# node.net
KiCad netlist of a schematic drawn in EAGLE
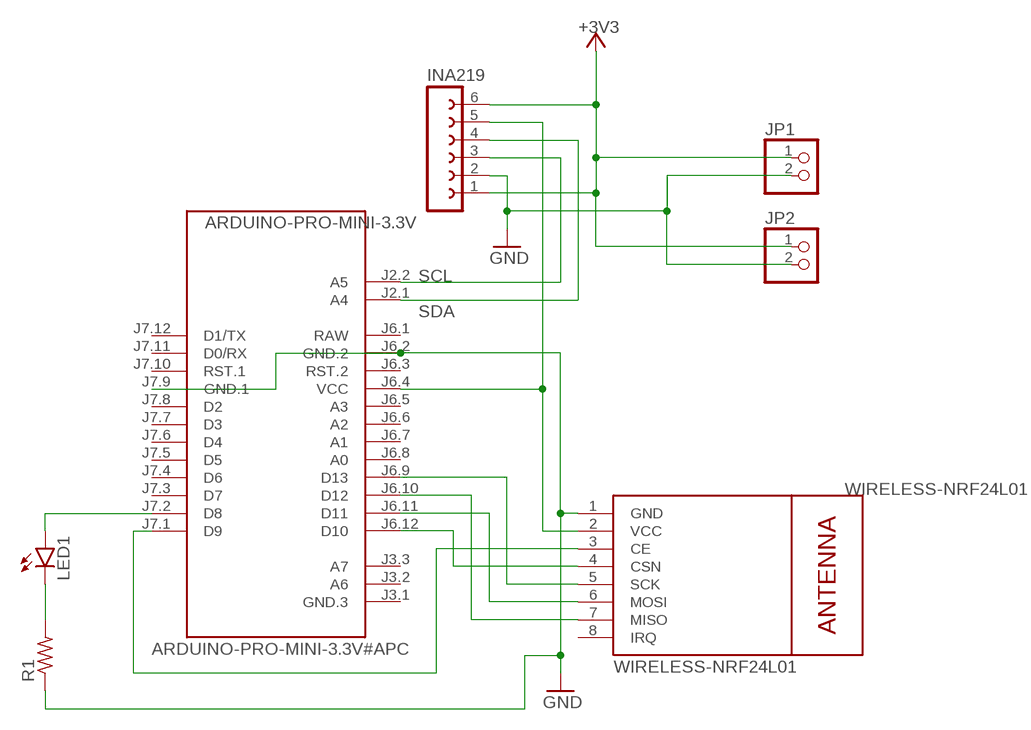
[diagram p0: schematic, sheet 1]

(export (version "E")
  (design (tool "Eeschema 10.0.6"))
  (components
    (comp (ref "ARDUINO-PRO-MINI-3.3V")
      (value "ARDUINO-PRO-MINI-3.3V#APC")
      (footprint "eagle-import:ARDUINO-PRO-MINI#APC")
      (libsource (lib "eagle-import") (part "ARDUINO-PRO-MINI-#APC3.3V"))
    )
    (comp (ref "INA219")
      (value "FE06-1")
      (footprint "eagle-import:FE06")
      (libsource (lib "eagle-import") (part "FE06-1"))
    )
    (comp (ref "JP1")
      (value "PINHD-1X2")
      (footprint "eagle-import:1X02")
      (libsource (lib "eagle-import") (part "PINHD-1X2"))
    )
    (comp (ref "JP2")
      (value "PINHD-1X2")
      (footprint "eagle-import:1X02")
      (libsource (lib "eagle-import") (part "PINHD-1X2"))
    )
    (comp (ref "LED1")
      (value "LED3MM")
      (footprint "eagle-import:LED3MM")
      (libsource (lib "eagle-import") (part "LED3MM"))
    )
    (comp (ref "R1")
      (value "R-US_0204/7")
      (footprint "eagle-import:0204_7")
      (libsource (lib "eagle-import") (part "R-US_0204/7"))
    )
    (comp (ref "WIRELESS-NRF24L01")
      (value "WIRELESS-NRF24L01")
      (footprint "eagle-import:WIRELESS-NRF24L01")
      (libsource (lib "eagle-import") (part "WIRELESS-NRF24L01"))
    )
  )
  (nets
    (net (code "1") (name "+3V3") (class "Default")
      (node (ref "INA219") (pin "1") (pinfunction "1_1") (pintype "passive"))
      (node (ref "INA219") (pin "6") (pinfunction "6_6") (pintype "passive"))
      (node (ref "JP1") (pin "1") (pinfunction "1_1") (pintype "passive"))
      (node (ref "JP2") (pin "1") (pinfunction "1_1") (pintype "passive"))
    )
    (net (code "2") (name "/RAW") (class "Default")
      (node (ref "ARDUINO-PRO-MINI-3.3V") (pin "J6.1") (pinfunction "RAW_J6.1") (pintype "power_in"))
    )
    (net (code "3") (name "/SCL") (class "Default")
      (node (ref "ARDUINO-PRO-MINI-3.3V") (pin "J2.2") (pinfunction "A5_J2.2") (pintype "bidirectional"))
      (node (ref "INA219") (pin "3") (pinfunction "3_3") (pintype "passive"))
    )
    (net (code "4") (name "/SDA") (class "Default")
      (node (ref "ARDUINO-PRO-MINI-3.3V") (pin "J2.1") (pinfunction "A4_J2.1") (pintype "bidirectional"))
      (node (ref "INA219") (pin "4") (pinfunction "4_4") (pintype "passive"))
    )
    (net (code "5") (name "GND") (class "Default")
      (node (ref "ARDUINO-PRO-MINI-3.3V") (pin "J6.2") (pinfunction "GND.2_J6.2") (pintype "power_in"))
      (node (ref "ARDUINO-PRO-MINI-3.3V") (pin "J7.9") (pinfunction "GND.1_J7.9") (pintype "power_in"))
      (node (ref "INA219") (pin "2") (pinfunction "2_2") (pintype "passive"))
      (node (ref "JP1") (pin "2") (pinfunction "2_2") (pintype "passive"))
      (node (ref "JP2") (pin "2") (pinfunction "2_2") (pintype "passive"))
      (node (ref "R1") (pin "1") (pinfunction "1_1") (pintype "passive"))
      (node (ref "WIRELESS-NRF24L01") (pin "1") (pinfunction "GND_1") (pintype "power_in"))
    )
    (net (code "6") (name "Net-(ARDUINO-PRO-MINI-3.3V-D8)") (class "Default")
      (node (ref "ARDUINO-PRO-MINI-3.3V") (pin "J7.2") (pinfunction "D8_J7.2") (pintype "bidirectional"))
      (node (ref "LED1") (pin "A") (pinfunction "A_A") (pintype "passive"))
    )
    (net (code "7") (name "Net-(ARDUINO-PRO-MINI-3.3V-D9)") (class "Default")
      (node (ref "ARDUINO-PRO-MINI-3.3V") (pin "J7.1") (pinfunction "D9_J7.1") (pintype "bidirectional"))
      (node (ref "WIRELESS-NRF24L01") (pin "3") (pinfunction "CE_3") (pintype "bidirectional"))
    )
    (net (code "8") (name "Net-(ARDUINO-PRO-MINI-3.3V-D10)") (class "Default")
      (node (ref "ARDUINO-PRO-MINI-3.3V") (pin "J6.12") (pinfunction "D10_J6.12") (pintype "bidirectional"))
      (node (ref "WIRELESS-NRF24L01") (pin "4") (pinfunction "CSN_4") (pintype "bidirectional"))
    )
    (net (code "9") (name "Net-(ARDUINO-PRO-MINI-3.3V-D11)") (class "Default")
      (node (ref "ARDUINO-PRO-MINI-3.3V") (pin "J6.11") (pinfunction "D11_J6.11") (pintype "bidirectional"))
      (node (ref "WIRELESS-NRF24L01") (pin "6") (pinfunction "MOSI_6") (pintype "bidirectional"))
    )
    (net (code "10") (name "Net-(ARDUINO-PRO-MINI-3.3V-D12)") (class "Default")
      (node (ref "ARDUINO-PRO-MINI-3.3V") (pin "J6.10") (pinfunction "D12_J6.10") (pintype "bidirectional"))
      (node (ref "WIRELESS-NRF24L01") (pin "7") (pinfunction "MISO_7") (pintype "bidirectional"))
    )
    (net (code "11") (name "Net-(ARDUINO-PRO-MINI-3.3V-D13)") (class "Default")
      (node (ref "ARDUINO-PRO-MINI-3.3V") (pin "J6.9") (pinfunction "D13_J6.9") (pintype "bidirectional"))
      (node (ref "WIRELESS-NRF24L01") (pin "5") (pinfunction "SCK_5") (pintype "bidirectional"))
    )
    (net (code "12") (name "Net-(ARDUINO-PRO-MINI-3.3V-VCC)") (class "Default")
      (node (ref "ARDUINO-PRO-MINI-3.3V") (pin "J6.4") (pinfunction "VCC_J6.4") (pintype "power_in"))
      (node (ref "INA219") (pin "5") (pinfunction "5_5") (pintype "passive"))
      (node (ref "WIRELESS-NRF24L01") (pin "2") (pinfunction "VCC_2") (pintype "power_in"))
    )
    (net (code "13") (name "Net-(LED1-C)") (class "Default")
      (node (ref "LED1") (pin "K") (pinfunction "C_K") (pintype "passive"))
      (node (ref "R1") (pin "2") (pinfunction "2_2") (pintype "passive"))
    )
    (net (code "14") (name "unconnected-(ARDUINO-PRO-MINI-3.3V-A0-PadJ6.8)") (class "Default")
      (node (ref "ARDUINO-PRO-MINI-3.3V") (pin "J6.8") (pinfunction "A0_J6.8") (pintype "bidirectional"))
    )
    (net (code "15") (name "unconnected-(ARDUINO-PRO-MINI-3.3V-A1-PadJ6.7)") (class "Default")
      (node (ref "ARDUINO-PRO-MINI-3.3V") (pin "J6.7") (pinfunction "A1_J6.7") (pintype "bidirectional"))
    )
    (net (code "16") (name "unconnected-(ARDUINO-PRO-MINI-3.3V-A2-PadJ6.6)") (class "Default")
      (node (ref "ARDUINO-PRO-MINI-3.3V") (pin "J6.6") (pinfunction "A2_J6.6") (pintype "bidirectional"))
    )
    (net (code "17") (name "unconnected-(ARDUINO-PRO-MINI-3.3V-A3-PadJ6.5)") (class "Default")
      (node (ref "ARDUINO-PRO-MINI-3.3V") (pin "J6.5") (pinfunction "A3_J6.5") (pintype "bidirectional"))
    )
    (net (code "18") (name "unconnected-(ARDUINO-PRO-MINI-3.3V-A6-PadJ3.2)") (class "Default")
      (node (ref "ARDUINO-PRO-MINI-3.3V") (pin "J3.2") (pinfunction "A6_J3.2") (pintype "bidirectional"))
    )
    (net (code "19") (name "unconnected-(ARDUINO-PRO-MINI-3.3V-A7-PadJ3.3)") (class "Default")
      (node (ref "ARDUINO-PRO-MINI-3.3V") (pin "J3.3") (pinfunction "A7_J3.3") (pintype "bidirectional"))
    )
    (net (code "20") (name "unconnected-(ARDUINO-PRO-MINI-3.3V-D0{slash}RX-PadJ7.11)") (class "Default")
      (node (ref "ARDUINO-PRO-MINI-3.3V") (pin "J7.11") (pinfunction "D0/RX_J7.11") (pintype "bidirectional"))
    )
    (net (code "21") (name "unconnected-(ARDUINO-PRO-MINI-3.3V-D1{slash}TX-PadJ7.12)") (class "Default")
      (node (ref "ARDUINO-PRO-MINI-3.3V") (pin "J7.12") (pinfunction "D1/TX_J7.12") (pintype "bidirectional"))
    )
    (net (code "22") (name "unconnected-(ARDUINO-PRO-MINI-3.3V-D2-PadJ7.8)") (class "Default")
      (node (ref "ARDUINO-PRO-MINI-3.3V") (pin "J7.8") (pinfunction "D2_J7.8") (pintype "bidirectional"))
    )
    (net (code "23") (name "unconnected-(ARDUINO-PRO-MINI-3.3V-D3-PadJ7.7)") (class "Default")
      (node (ref "ARDUINO-PRO-MINI-3.3V") (pin "J7.7") (pinfunction "D3_J7.7") (pintype "bidirectional"))
    )
    (net (code "24") (name "unconnected-(ARDUINO-PRO-MINI-3.3V-D4-PadJ7.6)") (class "Default")
      (node (ref "ARDUINO-PRO-MINI-3.3V") (pin "J7.6") (pinfunction "D4_J7.6") (pintype "bidirectional"))
    )
    (net (code "25") (name "unconnected-(ARDUINO-PRO-MINI-3.3V-D5-PadJ7.5)") (class "Default")
      (node (ref "ARDUINO-PRO-MINI-3.3V") (pin "J7.5") (pinfunction "D5_J7.5") (pintype "bidirectional"))
    )
    (net (code "26") (name "unconnected-(ARDUINO-PRO-MINI-3.3V-D6-PadJ7.4)") (class "Default")
      (node (ref "ARDUINO-PRO-MINI-3.3V") (pin "J7.4") (pinfunction "D6_J7.4") (pintype "bidirectional"))
    )
    (net (code "27") (name "unconnected-(ARDUINO-PRO-MINI-3.3V-D7-PadJ7.3)") (class "Default")
      (node (ref "ARDUINO-PRO-MINI-3.3V") (pin "J7.3") (pinfunction "D7_J7.3") (pintype "bidirectional"))
    )
    (net (code "28") (name "unconnected-(ARDUINO-PRO-MINI-3.3V-GND.3-PadJ3.1)") (class "Default")
      (node (ref "ARDUINO-PRO-MINI-3.3V") (pin "J3.1") (pinfunction "GND.3_J3.1") (pintype "bidirectional"))
    )
    (net (code "29") (name "unconnected-(ARDUINO-PRO-MINI-3.3V-RST.1-PadJ7.10)") (class "Default")
      (node (ref "ARDUINO-PRO-MINI-3.3V") (pin "J7.10") (pinfunction "RST.1_J7.10") (pintype "bidirectional"))
    )
    (net (code "30") (name "unconnected-(ARDUINO-PRO-MINI-3.3V-RST.2-PadJ6.3)") (class "Default")
      (node (ref "ARDUINO-PRO-MINI-3.3V") (pin "J6.3") (pinfunction "RST.2_J6.3") (pintype "bidirectional"))
    )
    (net (code "31") (name "unconnected-(WIRELESS-NRF24L01-IRQ-Pad8)") (class "Default")
      (node (ref "WIRELESS-NRF24L01") (pin "8") (pinfunction "IRQ_8") (pintype "bidirectional"))
    )
  )
)
